# A3_3V.net
KiCad netlist of a schematic drawn in Altium Designer
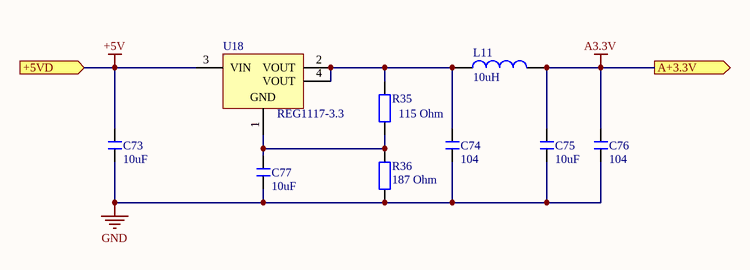
[diagram p0: A3.3V.SchDoc]

(export (version "E")
  (design (tool "Eeschema 10.0.6"))
  (components
    (comp (ref "C73")
      (value "10uF")
      (footprint "C 0805_L")
      (description "贴片电容")
      (libsource (lib "0.1 - 电阻-电容-电感") (part "C"))
    )
    (comp (ref "C74")
      (value "104")
      (footprint "C 0805_L")
      (description "贴片电容")
      (libsource (lib "0.1 - 电阻-电容-电感") (part "C"))
    )
    (comp (ref "C75")
      (value "10uF")
      (footprint "C 0805_L")
      (description "贴片电容")
      (libsource (lib "0.1 - 电阻-电容-电感") (part "C"))
    )
    (comp (ref "C76")
      (value "104")
      (footprint "C 0805_L")
      (description "贴片电容")
      (libsource (lib "0.1 - 电阻-电容-电感") (part "C"))
    )
    (comp (ref "C77")
      (value "10uF")
      (footprint "C 0805_L")
      (description "贴片电容")
      (libsource (lib "0.1 - 电阻-电容-电感") (part "C"))
    )
    (comp (ref "L11")
      (value "10uH")
      (footprint "AL0307")
      (description "色环电感")
      (libsource (lib "0.1 - 电阻-电容-电感") (part "L-AL"))
    )
    (comp (ref "R35")
      (value "115 Ohm")
      (footprint "R 0805_L")
      (description "贴片电阻")
      (fields (field (name "版权归属") "来自淘宝 ID：黄晶宝石"))
      (libsource (lib "0.1 - 电阻-电容-电感") (part "R"))
    )
    (comp (ref "R36")
      (value "187 Ohm")
      (footprint "R 0805_L")
      (description "贴片电阻")
      (fields (field (name "版权归属") "来自淘宝 ID：黄晶宝石"))
      (libsource (lib "0.1 - 电阻-电容-电感") (part "R"))
    )
    (comp (ref "U18")
      (value "REG1117-3.3")
      (footprint "DCY0004A_M")
      (fields (field (name "MANUFACTURER") "Texas Instruments"))
      (libsource (lib "Components - 22.10.23 - 20.31") (part "CMP-0395-00549-2"))
    )
  )
  (nets
    (net (code "1") (name "+5V") (class "Default")
      (node (ref "C73") (pin "2") (pinfunction "2_2") (pintype "passive"))
      (node (ref "U18") (pin "3") (pinfunction "VIN_3") (pintype "passive"))
    )
    (net (code "2") (name "A3.3V") (class "Default")
      (node (ref "C75") (pin "2") (pinfunction "2_2") (pintype "passive"))
      (node (ref "C76") (pin "2") (pinfunction "2_2") (pintype "passive"))
      (node (ref "L11") (pin "2") (pinfunction "2_2") (pintype "passive"))
    )
    (net (code "3") (name "GND") (class "Default")
      (node (ref "C73") (pin "1") (pinfunction "1_1") (pintype "passive"))
      (node (ref "C74") (pin "1") (pinfunction "1_1") (pintype "passive"))
      (node (ref "C75") (pin "1") (pinfunction "1_1") (pintype "passive"))
      (node (ref "C76") (pin "1") (pinfunction "1_1") (pintype "passive"))
      (node (ref "C77") (pin "1") (pinfunction "1_1") (pintype "passive"))
      (node (ref "R36") (pin "1") (pinfunction "1_1") (pintype "passive"))
    )
    (net (code "4") (name "Net-(C74-Pad2)") (class "Default")
      (node (ref "C74") (pin "2") (pinfunction "2_2") (pintype "passive"))
      (node (ref "L11") (pin "1") (pinfunction "1_1") (pintype "passive"))
      (node (ref "R35") (pin "2") (pinfunction "2_2") (pintype "passive"))
      (node (ref "U18") (pin "2") (pinfunction "VOUT_2") (pintype "passive"))
      (node (ref "U18") (pin "4") (pinfunction "VOUT_4") (pintype "passive"))
    )
    (net (code "5") (name "Net-(U18-GND)") (class "Default")
      (node (ref "C77") (pin "2") (pinfunction "2_2") (pintype "passive"))
      (node (ref "R35") (pin "1") (pinfunction "1_1") (pintype "passive"))
      (node (ref "R36") (pin "2") (pinfunction "2_2") (pintype "passive"))
      (node (ref "U18") (pin "1") (pinfunction "GND_1") (pintype "power_in"))
    )
  )
)
